# BCD_7SD_Decoder_1_1.net
KiCad netlist of a schematic drawn in EAGLE
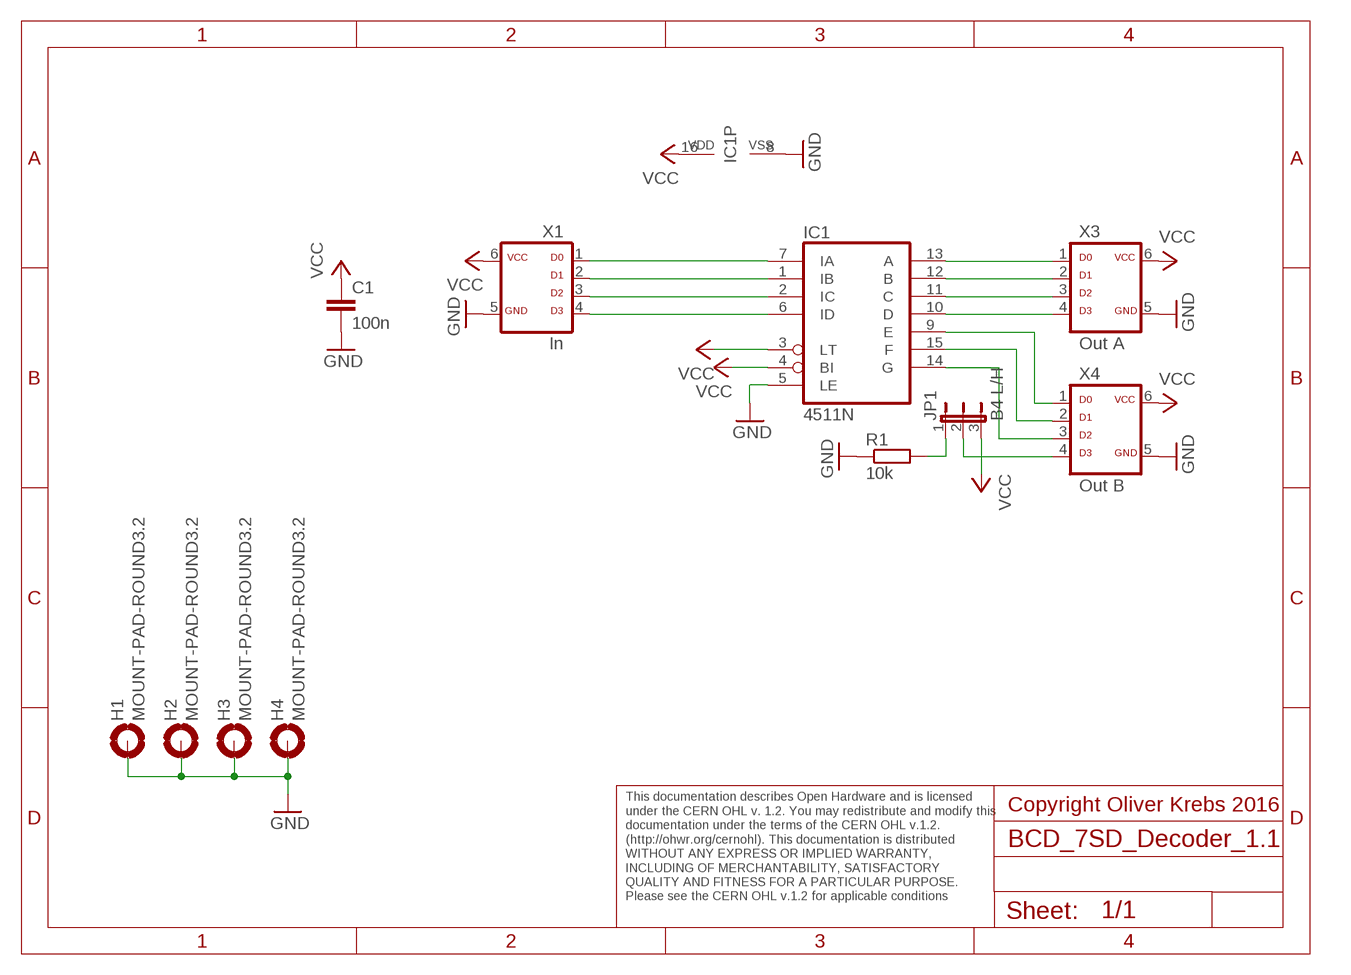
[diagram p0: schematic, sheet 1]

(export (version "E")
  (design (tool "Eeschema 10.0.6"))
  (components
    (comp (ref "C1")
      (value "100n")
      (footprint "eagle-import:C050-025X075")
      (libsource (lib "eagle-import") (part "C-EU050-025X075"))
    )
    (comp (ref "H1")
      (value "MOUNT-PAD-ROUND3.2")
      (footprint "eagle-import:3,2-PAD")
      (libsource (lib "eagle-import") (part "MOUNT-PAD-ROUND3.2"))
    )
    (comp (ref "H2")
      (value "MOUNT-PAD-ROUND3.2")
      (footprint "eagle-import:3,2-PAD")
      (libsource (lib "eagle-import") (part "MOUNT-PAD-ROUND3.2"))
    )
    (comp (ref "H3")
      (value "MOUNT-PAD-ROUND3.2")
      (footprint "eagle-import:3,2-PAD")
      (libsource (lib "eagle-import") (part "MOUNT-PAD-ROUND3.2"))
    )
    (comp (ref "H4")
      (value "MOUNT-PAD-ROUND3.2")
      (footprint "eagle-import:3,2-PAD")
      (libsource (lib "eagle-import") (part "MOUNT-PAD-ROUND3.2"))
    )
    (comp (ref "IC1")
      (value "4511N")
      (footprint "eagle-import:DIL16")
      (libsource (lib "eagle-import") (part "4511N"))
    )
    (comp (ref "JP1")
      (value "B4 L/H")
      (footprint "eagle-import:JP2")
      (libsource (lib "eagle-import") (part "JP2E"))
    )
    (comp (ref "R1")
      (value "10k")
      (footprint "eagle-import:0207_10")
      (libsource (lib "eagle-import") (part "R-EU_0207/10"))
    )
    (comp (ref "X1")
      (value "In")
      (footprint "eagle-import:ML-6")
      (libsource (lib "eagle-import") (part "ML6D"))
    )
    (comp (ref "X3")
      (value "Out A")
      (footprint "eagle-import:ML-6")
      (libsource (lib "eagle-import") (part "ML6D"))
    )
    (comp (ref "X4")
      (value "Out B")
      (footprint "eagle-import:ML-6")
      (libsource (lib "eagle-import") (part "ML6D"))
    )
  )
  (nets
    (net (code "1") (name "GND") (class "Default")
      (node (ref "C1") (pin "2") (pinfunction "2_2") (pintype "passive"))
      (node (ref "H1") (pin "B3,2") (pinfunction "MOUNT_B3,2") (pintype "passive"))
      (node (ref "H2") (pin "B3,2") (pinfunction "MOUNT_B3,2") (pintype "passive"))
      (node (ref "H3") (pin "B3,2") (pinfunction "MOUNT_B3,2") (pintype "passive"))
      (node (ref "H4") (pin "B3,2") (pinfunction "MOUNT_B3,2") (pintype "passive"))
      (node (ref "IC1") (pin "5") (pinfunction "LE_5") (pintype "input"))
      (node (ref "IC1") (pin "8") (pinfunction "VSS_8") (pintype "power_in"))
      (node (ref "R1") (pin "1") (pinfunction "1_1") (pintype "passive"))
      (node (ref "X1") (pin "5") (pinfunction "5_5") (pintype "passive"))
      (node (ref "X3") (pin "5") (pinfunction "5_5") (pintype "passive"))
      (node (ref "X4") (pin "5") (pinfunction "5_5") (pintype "passive"))
    )
    (net (code "2") (name "Net-(IC1A-A)") (class "Default")
      (node (ref "IC1") (pin "13") (pinfunction "A_13") (pintype "output"))
      (node (ref "X3") (pin "1") (pinfunction "1_1") (pintype "passive"))
    )
    (net (code "3") (name "Net-(IC1A-B)") (class "Default")
      (node (ref "IC1") (pin "12") (pinfunction "B_12") (pintype "output"))
      (node (ref "X3") (pin "2") (pinfunction "2_2") (pintype "passive"))
    )
    (net (code "4") (name "Net-(IC1A-C)") (class "Default")
      (node (ref "IC1") (pin "11") (pinfunction "C_11") (pintype "output"))
      (node (ref "X3") (pin "3") (pinfunction "3_3") (pintype "passive"))
    )
    (net (code "5") (name "Net-(IC1A-D)") (class "Default")
      (node (ref "IC1") (pin "10") (pinfunction "D_10") (pintype "output"))
      (node (ref "X3") (pin "4") (pinfunction "4_4") (pintype "passive"))
    )
    (net (code "6") (name "Net-(IC1A-E)") (class "Default")
      (node (ref "IC1") (pin "9") (pinfunction "E_9") (pintype "output"))
      (node (ref "X4") (pin "1") (pinfunction "1_1") (pintype "passive"))
    )
    (net (code "7") (name "Net-(IC1A-F)") (class "Default")
      (node (ref "IC1") (pin "15") (pinfunction "F_15") (pintype "output"))
      (node (ref "X4") (pin "2") (pinfunction "2_2") (pintype "passive"))
    )
    (net (code "8") (name "Net-(IC1A-G)") (class "Default")
      (node (ref "IC1") (pin "14") (pinfunction "G_14") (pintype "output"))
      (node (ref "X4") (pin "3") (pinfunction "3_3") (pintype "passive"))
    )
    (net (code "9") (name "Net-(IC1A-IA)") (class "Default")
      (node (ref "IC1") (pin "7") (pinfunction "IA_7") (pintype "input"))
      (node (ref "X1") (pin "1") (pinfunction "1_1") (pintype "passive"))
    )
    (net (code "10") (name "Net-(IC1A-IB)") (class "Default")
      (node (ref "IC1") (pin "1") (pinfunction "IB_1") (pintype "input"))
      (node (ref "X1") (pin "2") (pinfunction "2_2") (pintype "passive"))
    )
    (net (code "11") (name "Net-(IC1A-IC)") (class "Default")
      (node (ref "IC1") (pin "2") (pinfunction "IC_2") (pintype "input"))
      (node (ref "X1") (pin "3") (pinfunction "3_3") (pintype "passive"))
    )
    (net (code "12") (name "Net-(IC1A-ID)") (class "Default")
      (node (ref "IC1") (pin "6") (pinfunction "ID_6") (pintype "input"))
      (node (ref "X1") (pin "4") (pinfunction "4_4") (pintype "passive"))
    )
    (net (code "13") (name "Net-(JP1-Pad1)") (class "Default")
      (node (ref "JP1") (pin "1") (pinfunction "1_1") (pintype "passive"))
      (node (ref "R1") (pin "2") (pinfunction "2_2") (pintype "passive"))
    )
    (net (code "14") (name "Net-(JP1-Pad2)") (class "Default")
      (node (ref "JP1") (pin "2") (pinfunction "2_2") (pintype "passive"))
      (node (ref "X4") (pin "4") (pinfunction "4_4") (pintype "passive"))
    )
    (net (code "15") (name "VCC") (class "Default")
      (node (ref "C1") (pin "1") (pinfunction "1_1") (pintype "passive"))
      (node (ref "IC1") (pin "16") (pinfunction "VDD_16") (pintype "power_in"))
      (node (ref "IC1") (pin "3") (pinfunction "LT_3") (pintype "input"))
      (node (ref "IC1") (pin "4") (pinfunction "BI_4") (pintype "input"))
      (node (ref "JP1") (pin "3") (pinfunction "3_3") (pintype "passive"))
      (node (ref "X1") (pin "6") (pinfunction "6_6") (pintype "passive"))
      (node (ref "X3") (pin "6") (pinfunction "6_6") (pintype "passive"))
      (node (ref "X4") (pin "6") (pinfunction "6_6") (pintype "passive"))
    )
  )
)
